# LT3762EUFD.net
KiCad netlist of a schematic drawn in Altium Designer
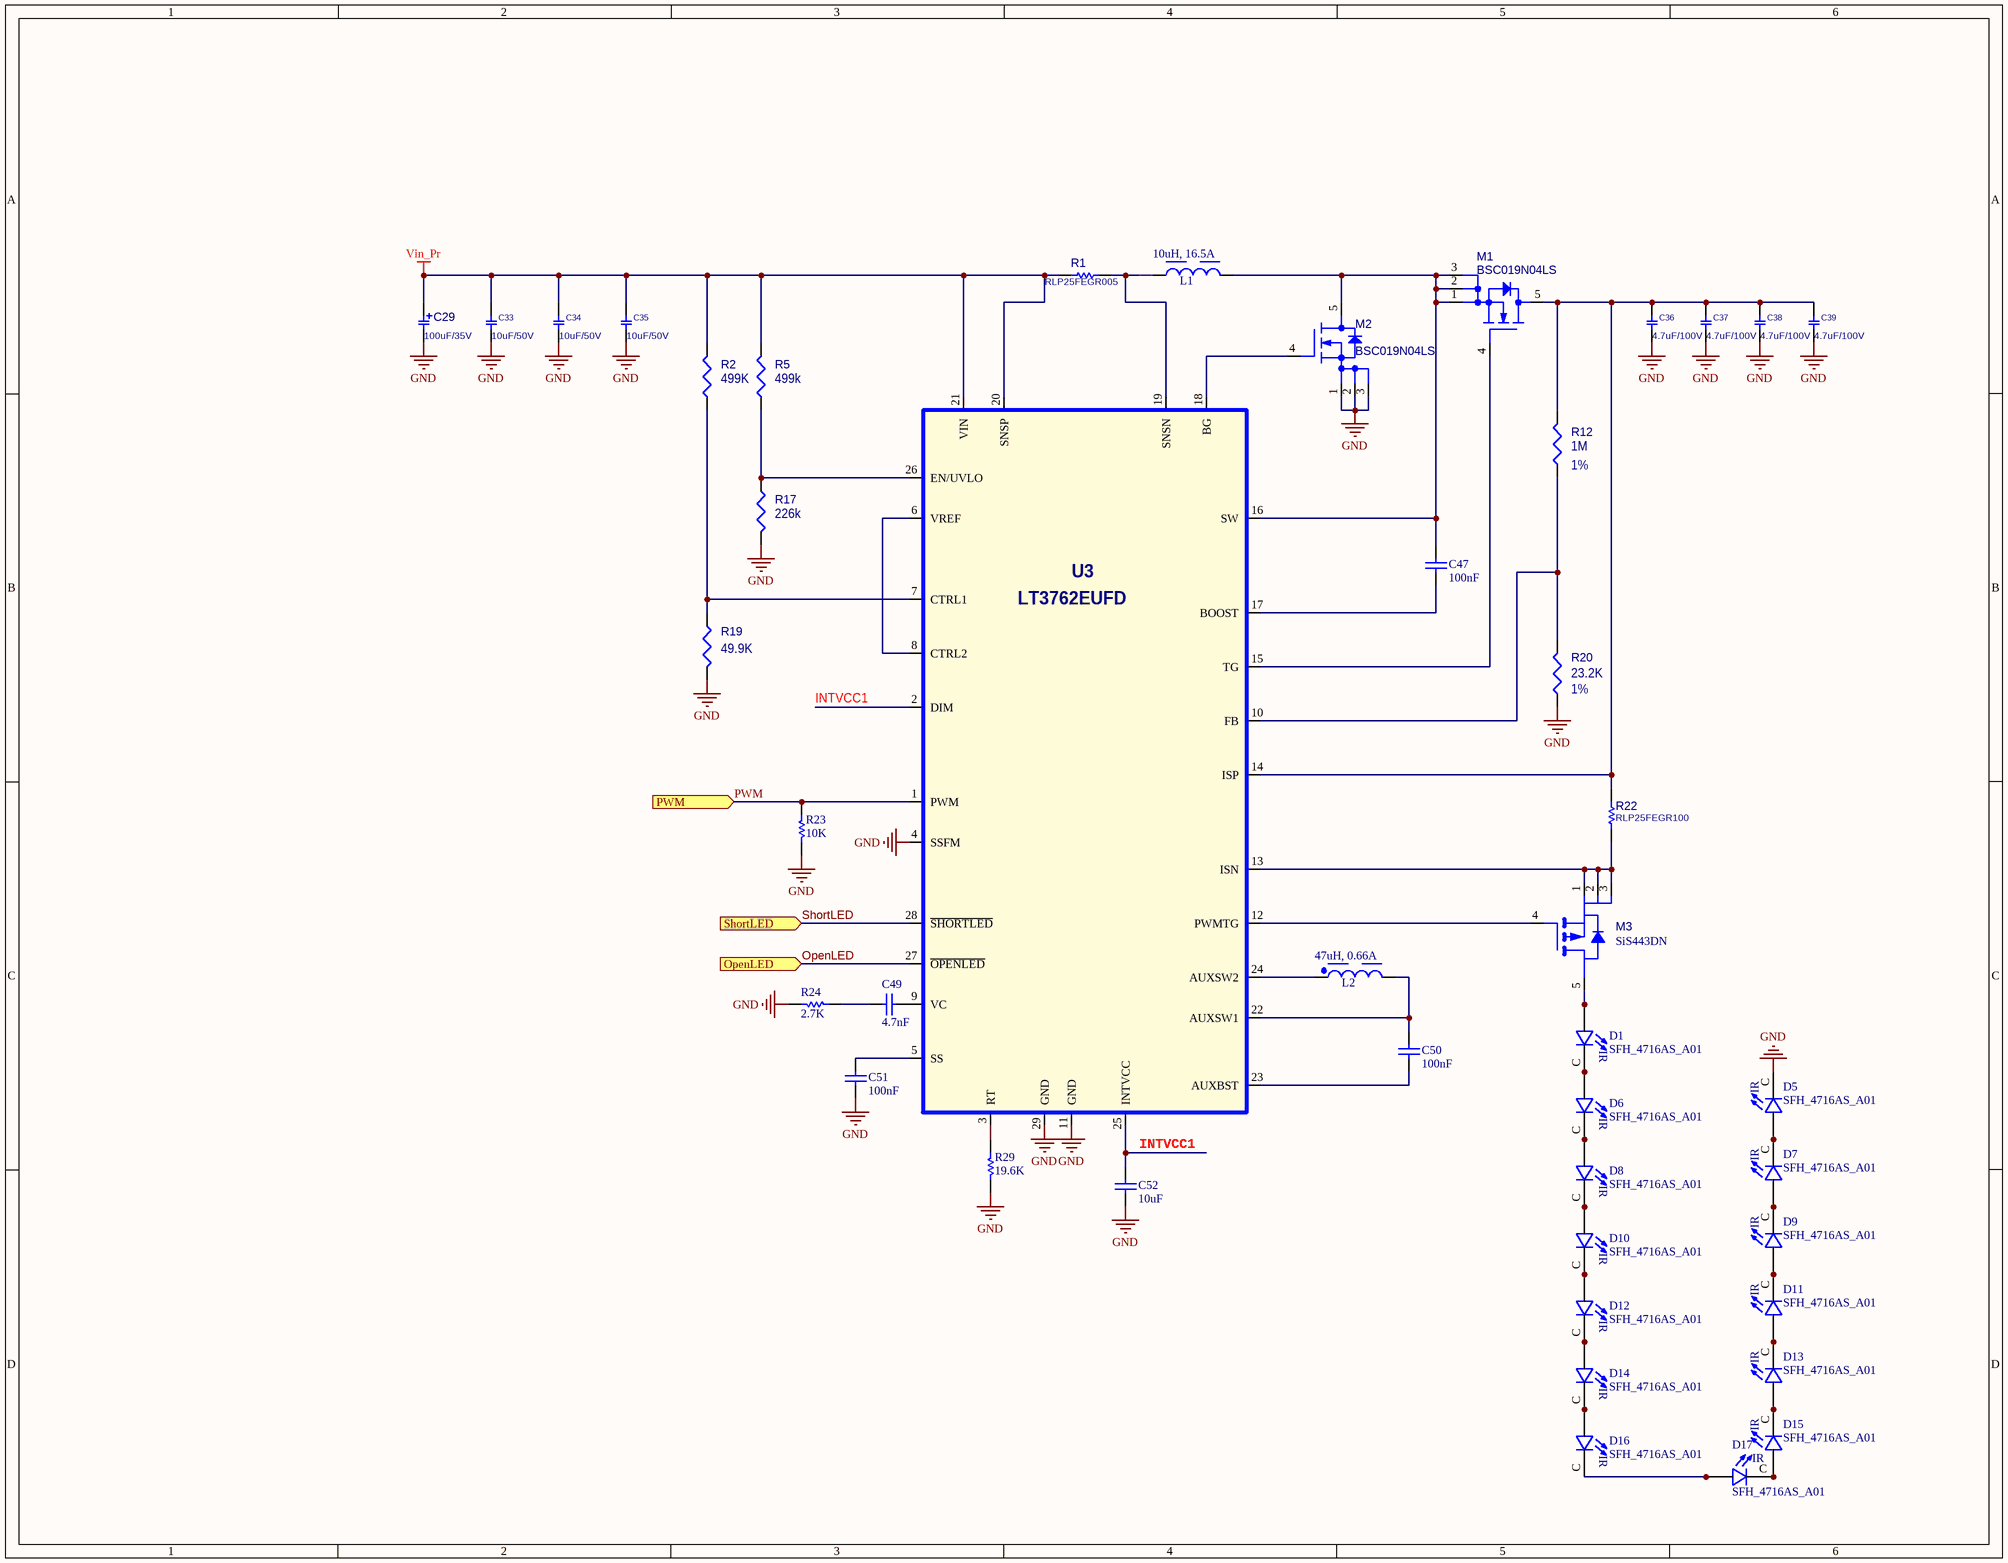
[diagram p0: LT3762EUFD.SchDoc]

(export (version "E")
  (design (tool "Eeschema 10.0.6"))
  (components
    (comp (ref "C29")
      (value "100uF/35V")
      (footprint "C_EL_D8L10")
      (description "CAP, SMD, ELEC,")
      (fields (field (name "MANF_P#") "MANF_PART#") (field (name "MANF") "MANF"))
      (libsource (lib "passive_smd") (part "CAP_SMD_EL_220uF_35v"))
    )
    (comp (ref "C33")
      (value "10uF/50V")
      (footprint "PASSIVE_SMD:C1210")
      (description "CAP, MLCC")
      (fields (field (name "MANF_P#") "MANF_PART#"))
      (libsource (lib "passive_smd") (part "CAP_SMD_MLCC_1210"))
    )
    (comp (ref "C34")
      (value "10uF/50V")
      (footprint "PASSIVE_SMD:C1210")
      (description "CAP, MLCC")
      (fields (field (name "MANF_P#") "MANF_PART#"))
      (libsource (lib "passive_smd") (part "CAP_SMD_MLCC_1210"))
    )
    (comp (ref "C35")
      (value "10uF/50V")
      (footprint "PASSIVE_SMD:C1210")
      (description "CAP, MLCC")
      (fields (field (name "MANF_P#") "MANF_PART#"))
      (libsource (lib "passive_smd") (part "CAP_SMD_MLCC_1210"))
    )
    (comp (ref "C36")
      (value "4.7uF/100V")
      (footprint "PASSIVE_SMD:C1210")
      (description "CAP, MLCC")
      (fields (field (name "MANF_P#") "MANF_PART#"))
      (libsource (lib "passive_smd") (part "CAP_SMD_MLCC_1210"))
    )
    (comp (ref "C37")
      (value "4.7uF/100V")
      (footprint "PASSIVE_SMD:C1210")
      (description "CAP, MLCC")
      (fields (field (name "MANF_P#") "MANF_PART#"))
      (libsource (lib "passive_smd") (part "CAP_SMD_MLCC_1210"))
    )
    (comp (ref "C38")
      (value "4.7uF/100V")
      (footprint "PASSIVE_SMD:C1210")
      (description "CAP, MLCC")
      (fields (field (name "MANF_P#") "MANF_PART#"))
      (libsource (lib "passive_smd") (part "CAP_SMD_MLCC_1210"))
    )
    (comp (ref "C39")
      (value "4.7uF/100V")
      (footprint "PASSIVE_SMD:C1210")
      (description "CAP, MLCC")
      (fields (field (name "MANF_P#") "MANF_PART#"))
      (libsource (lib "passive_smd") (part "CAP_SMD_MLCC_1210"))
    )
    (comp (ref "C47")
      (value "100nF")
      (footprint "C0603")
      (fields (field (name "PUBLISHER") "Altium Limited"))
      (libsource (lib "Miscellaneous Devices") (part "CAP"))
    )
    (comp (ref "C49")
      (value "4.7nF")
      (footprint "C0603")
      (fields (field (name "PUBLISHER") "Altium Limited"))
      (libsource (lib "Miscellaneous Devices") (part "CAP"))
    )
    (comp (ref "C50")
      (value "100nF")
      (footprint "C0603")
      (fields (field (name "PUBLISHER") "Altium Limited"))
      (libsource (lib "Miscellaneous Devices") (part "CAP"))
    )
    (comp (ref "C51")
      (value "100nF")
      (footprint "C0603")
      (fields (field (name "PUBLISHER") "Altium Limited"))
      (libsource (lib "Miscellaneous Devices") (part "CAP"))
    )
    (comp (ref "C52")
      (value "10uF")
      (footprint "C0603")
      (fields (field (name "PUBLISHER") "Altium Limited"))
      (libsource (lib "Miscellaneous Devices") (part "CAP"))
    )
    (comp (ref "D1")
      (value "SFH_4716AS_A01")
      (footprint "LED_SFH_4716AS_A01")
      (description "OSLON Black Series (850 nm) - 150Â°")
      (libsource (lib "SFH_4716AS_A01") (part "SFH_4716AS_A01"))
    )
    (comp (ref "D5")
      (value "SFH_4716AS_A01")
      (footprint "LED_SFH_4716AS_A01")
      (description "OSLON Black Series (850 nm) - 150Â°")
      (libsource (lib "SFH_4716AS_A01") (part "SFH_4716AS_A01"))
    )
    (comp (ref "D6")
      (value "SFH_4716AS_A01")
      (footprint "LED_SFH_4716AS_A01")
      (description "OSLON Black Series (850 nm) - 150Â°")
      (libsource (lib "SFH_4716AS_A01") (part "SFH_4716AS_A01"))
    )
    (comp (ref "D7")
      (value "SFH_4716AS_A01")
      (footprint "LED_SFH_4716AS_A01")
      (description "OSLON Black Series (850 nm) - 150Â°")
      (libsource (lib "SFH_4716AS_A01") (part "SFH_4716AS_A01"))
    )
    (comp (ref "D8")
      (value "SFH_4716AS_A01")
      (footprint "LED_SFH_4716AS_A01")
      (description "OSLON Black Series (850 nm) - 150Â°")
      (libsource (lib "SFH_4716AS_A01") (part "SFH_4716AS_A01"))
    )
    (comp (ref "D9")
      (value "SFH_4716AS_A01")
      (footprint "LED_SFH_4716AS_A01")
      (description "OSLON Black Series (850 nm) - 150Â°")
      (libsource (lib "SFH_4716AS_A01") (part "SFH_4716AS_A01"))
    )
    (comp (ref "D10")
      (value "SFH_4716AS_A01")
      (footprint "LED_SFH_4716AS_A01")
      (description "OSLON Black Series (850 nm) - 150Â°")
      (libsource (lib "SFH_4716AS_A01") (part "SFH_4716AS_A01"))
    )
    (comp (ref "D11")
      (value "SFH_4716AS_A01")
      (footprint "LED_SFH_4716AS_A01")
      (description "OSLON Black Series (850 nm) - 150Â°")
      (libsource (lib "SFH_4716AS_A01") (part "SFH_4716AS_A01"))
    )
    (comp (ref "D12")
      (value "SFH_4716AS_A01")
      (footprint "LED_SFH_4716AS_A01")
      (description "OSLON Black Series (850 nm) - 150Â°")
      (libsource (lib "SFH_4716AS_A01") (part "SFH_4716AS_A01"))
    )
    (comp (ref "D13")
      (value "SFH_4716AS_A01")
      (footprint "LED_SFH_4716AS_A01")
      (description "OSLON Black Series (850 nm) - 150Â°")
      (libsource (lib "SFH_4716AS_A01") (part "SFH_4716AS_A01"))
    )
    (comp (ref "D14")
      (value "SFH_4716AS_A01")
      (footprint "LED_SFH_4716AS_A01")
      (description "OSLON Black Series (850 nm) - 150Â°")
      (libsource (lib "SFH_4716AS_A01") (part "SFH_4716AS_A01"))
    )
    (comp (ref "D15")
      (value "SFH_4716AS_A01")
      (footprint "LED_SFH_4716AS_A01")
      (description "OSLON Black Series (850 nm) - 150Â°")
      (libsource (lib "SFH_4716AS_A01") (part "SFH_4716AS_A01"))
    )
    (comp (ref "D16")
      (value "SFH_4716AS_A01")
      (footprint "LED_SFH_4716AS_A01")
      (description "OSLON Black Series (850 nm) - 150Â°")
      (libsource (lib "SFH_4716AS_A01") (part "SFH_4716AS_A01"))
    )
    (comp (ref "D17")
      (value "SFH_4716AS_A01")
      (footprint "LED_SFH_4716AS_A01")
      (description "OSLON Black Series (850 nm) - 150Â°")
      (libsource (lib "SFH_4716AS_A01") (part "SFH_4716AS_A01"))
    )
    (comp (ref "L1")
      (value "10uH, 16.5A")
      (footprint "WE-HCI_1890")
      (description "WE-HCI SMT Flat Wire High Current Inductor, size 1890, 10uH, 16.5A, 6.9mOhm")
      (fields
        (field (name "MANUFACTURER PART NUMBER") "74435561100")
        (field (name "MANUFACTURER") "Wurth Elektronik")
      )
      (libsource (lib "WE - Passive Components") (part "Inductor - 3"))
    )
    (comp (ref "L2")
      (value "47uH, 0.66A")
      (footprint "WE-SPC_4828")
      (description "WE-SPC SMT Power Inductor, size 4828, 47uH, 0.66A, 0.608Ohm")
      (fields
        (field (name "MANUFACTURER PART NUMBER") "74408942470")
        (field (name "MANUFACTURER") "Wurth Elektronik")
      )
      (libsource (lib "WE - Passive Components") (part "Inductor - 2"))
    )
    (comp (ref "M1") (value "BSC019N04LS") (footprint "PG-TDSON-8") (libsource (lib "*") (part "2N7000_6")))
    (comp (ref "M2") (value "BSC019N04LS") (footprint "PG-TDSON-8") (libsource (lib "*") (part "2N7000_6")))
    (comp (ref "M3")
      (value "SiS443DN")
      (footprint "POWERPAK-1212-8-S-5P")
      (libsource (lib "*") (part "SI4463BDY_1"))
    )
    (comp (ref "R1")
      (value "RLP25FEGR005")
      (footprint "R2512")
      (description "3W 5mΩ ±50ppm/℃ ±1% 2512 Current Sense Shunt Resistors")
      (libsource (lib "passive_smd") (part "RES_SMD_2512"))
    )
    (comp (ref "R2") (value "499K") (footprint "R0603") (libsource (lib "*") (part "RES0402")))
    (comp (ref "R5") (value "499k") (footprint "R0603") (libsource (lib "*") (part "RES0402")))
    (comp (ref "R12")
      (value "1M")
      (footprint "R0603")
      (fields (field (name "6TH PART FIELD") "1%"))
      (libsource (lib "*") (part "RES0402"))
    )
    (comp (ref "R17") (value "226k") (footprint "R0603") (libsource (lib "*") (part "RES0402")))
    (comp (ref "R19") (value "49.9K") (footprint "R0603") (libsource (lib "*") (part "RES0402")))
    (comp (ref "R20")
      (value "23.2K")
      (footprint "R0603")
      (fields (field (name "6TH PART FIELD") "1%"))
      (libsource (lib "*") (part "RES0402"))
    )
    (comp (ref "R22")
      (value "RLP25FEGR100")
      (footprint "R2512")
      (description "3W 100mΩ ±50ppm/℃ ±1% 2512 Current Sense Shunt Resistors")
      (libsource (lib "passive_smd") (part "RES_SMD_2512"))
    )
    (comp (ref "R23")
      (value "10K")
      (footprint "R0603")
      (fields (field (name "PUBLISHER") "Altium Limited"))
      (libsource (lib "Miscellaneous Devices") (part "Res1"))
    )
    (comp (ref "R24")
      (value "2.7K")
      (footprint "R0603")
      (fields (field (name "PUBLISHER") "Altium Limited"))
      (libsource (lib "Miscellaneous Devices") (part "Res1"))
    )
    (comp (ref "R29")
      (value "19.6K")
      (footprint "R0603")
      (fields (field (name "PUBLISHER") "Altium Limited"))
      (libsource (lib "Miscellaneous Devices") (part "Res1"))
    )
    (comp (ref "U3")
      (value "LT3762EUFD")
      (footprint "QFN-28-4X5")
      (libsource (lib "*") (part "LT3932EFE_37"))
    )
  )
  (nets
    (net (code "1") (name "/INTVCC1") (class "Default")
      (node (ref "C52") (pin "1") (pinfunction "1_1") (pintype "passive"))
      (node (ref "U3") (pin "2") (pinfunction "DIM_2") (pintype "passive"))
      (node (ref "U3") (pin "25") (pinfunction "INTVCC_25") (pintype "passive"))
    )
    (net (code "2") (name "/OpenLED") (class "Default")
      (node (ref "U3") (pin "27") (pinfunction "~{OPENLED}_27") (pintype "passive"))
    )
    (net (code "3") (name "/PWM") (class "Default")
      (node (ref "R23") (pin "1") (pinfunction "1_1") (pintype "passive"))
      (node (ref "U3") (pin "1") (pinfunction "PWM_1") (pintype "passive"))
    )
    (net (code "4") (name "/ShortLED") (class "Default")
      (node (ref "U3") (pin "28") (pinfunction "~{SHORTLED}_28") (pintype "passive"))
    )
    (net (code "5") (name "GND") (class "Default")
      (node (ref "C29") (pin "2") (pinfunction "2_2") (pintype "passive"))
      (node (ref "C33") (pin "1") (pinfunction "1_1") (pintype "passive"))
      (node (ref "C34") (pin "1") (pinfunction "1_1") (pintype "passive"))
      (node (ref "C35") (pin "1") (pinfunction "1_1") (pintype "passive"))
      (node (ref "C36") (pin "1") (pinfunction "1_1") (pintype "passive"))
      (node (ref "C37") (pin "1") (pinfunction "1_1") (pintype "passive"))
      (node (ref "C38") (pin "1") (pinfunction "1_1") (pintype "passive"))
      (node (ref "C39") (pin "1") (pinfunction "1_1") (pintype "passive"))
      (node (ref "C51") (pin "2") (pinfunction "2_2") (pintype "passive"))
      (node (ref "C52") (pin "2") (pinfunction "2_2") (pintype "passive"))
      (node (ref "D5") (pin "C") (pinfunction "C_C") (pintype "passive"))
      (node (ref "M2") (pin "1") (pinfunction "SOURCE_1") (pintype "passive"))
      (node (ref "M2") (pin "2") (pinfunction "SOURCE_2") (pintype "passive"))
      (node (ref "M2") (pin "3") (pinfunction "SOURCE_3") (pintype "passive"))
      (node (ref "R17") (pin "1") (pinfunction "1_1") (pintype "passive"))
      (node (ref "R19") (pin "2") (pinfunction "2_2") (pintype "passive"))
      (node (ref "R20") (pin "1") (pinfunction "1_1") (pintype "passive"))
      (node (ref "R23") (pin "2") (pinfunction "2_2") (pintype "passive"))
      (node (ref "R24") (pin "2") (pinfunction "2_2") (pintype "passive"))
      (node (ref "R29") (pin "2") (pinfunction "2_2") (pintype "passive"))
      (node (ref "U3") (pin "11") (pinfunction "GND_11") (pintype "passive"))
      (node (ref "U3") (pin "29") (pinfunction "GND_29") (pintype "passive"))
      (node (ref "U3") (pin "4") (pinfunction "SSFM_4") (pintype "passive"))
    )
    (net (code "6") (name "Net-(C49-Pad2)") (class "Default")
      (node (ref "C49") (pin "2") (pinfunction "2_2") (pintype "passive"))
      (node (ref "R24") (pin "1") (pinfunction "1_1") (pintype "passive"))
    )
    (net (code "7") (name "Net-(D1-A-PadA1)") (class "Default")
      (node (ref "D1") (pin "A1") (pinfunction "A_A1") (pintype "passive"))
      (node (ref "D1") (pin "A2") (pinfunction "A_A2") (pintype "passive"))
      (node (ref "M3") (pin "5") (pinfunction "5_5") (pintype "passive"))
    )
    (net (code "8") (name "Net-(D1-PadC)") (class "Default")
      (node (ref "D1") (pin "C") (pinfunction "C_C") (pintype "passive"))
      (node (ref "D6") (pin "A1") (pinfunction "A_A1") (pintype "passive"))
      (node (ref "D6") (pin "A2") (pinfunction "A_A2") (pintype "passive"))
    )
    (net (code "9") (name "Net-(D5-A-PadA1)") (class "Default")
      (node (ref "D5") (pin "A1") (pinfunction "A_A1") (pintype "passive"))
      (node (ref "D5") (pin "A2") (pinfunction "A_A2") (pintype "passive"))
      (node (ref "D7") (pin "C") (pinfunction "C_C") (pintype "passive"))
    )
    (net (code "10") (name "Net-(D6-PadC)") (class "Default")
      (node (ref "D6") (pin "C") (pinfunction "C_C") (pintype "passive"))
      (node (ref "D8") (pin "A1") (pinfunction "A_A1") (pintype "passive"))
      (node (ref "D8") (pin "A2") (pinfunction "A_A2") (pintype "passive"))
    )
    (net (code "11") (name "Net-(D7-A-PadA1)") (class "Default")
      (node (ref "D7") (pin "A1") (pinfunction "A_A1") (pintype "passive"))
      (node (ref "D7") (pin "A2") (pinfunction "A_A2") (pintype "passive"))
      (node (ref "D9") (pin "C") (pinfunction "C_C") (pintype "passive"))
    )
    (net (code "12") (name "Net-(D10-A-PadA1)") (class "Default")
      (node (ref "D10") (pin "A1") (pinfunction "A_A1") (pintype "passive"))
      (node (ref "D10") (pin "A2") (pinfunction "A_A2") (pintype "passive"))
      (node (ref "D8") (pin "C") (pinfunction "C_C") (pintype "passive"))
    )
    (net (code "13") (name "Net-(D10-PadC)") (class "Default")
      (node (ref "D10") (pin "C") (pinfunction "C_C") (pintype "passive"))
      (node (ref "D12") (pin "A1") (pinfunction "A_A1") (pintype "passive"))
      (node (ref "D12") (pin "A2") (pinfunction "A_A2") (pintype "passive"))
    )
    (net (code "14") (name "Net-(D11-A-PadA1)") (class "Default")
      (node (ref "D11") (pin "A1") (pinfunction "A_A1") (pintype "passive"))
      (node (ref "D11") (pin "A2") (pinfunction "A_A2") (pintype "passive"))
      (node (ref "D13") (pin "C") (pinfunction "C_C") (pintype "passive"))
    )
    (net (code "15") (name "Net-(D11-PadC)") (class "Default")
      (node (ref "D11") (pin "C") (pinfunction "C_C") (pintype "passive"))
      (node (ref "D9") (pin "A1") (pinfunction "A_A1") (pintype "passive"))
      (node (ref "D9") (pin "A2") (pinfunction "A_A2") (pintype "passive"))
    )
    (net (code "16") (name "Net-(D12-PadC)") (class "Default")
      (node (ref "D12") (pin "C") (pinfunction "C_C") (pintype "passive"))
      (node (ref "D14") (pin "A1") (pinfunction "A_A1") (pintype "passive"))
      (node (ref "D14") (pin "A2") (pinfunction "A_A2") (pintype "passive"))
    )
    (net (code "17") (name "Net-(D13-A-PadA1)") (class "Default")
      (node (ref "D13") (pin "A1") (pinfunction "A_A1") (pintype "passive"))
      (node (ref "D13") (pin "A2") (pinfunction "A_A2") (pintype "passive"))
      (node (ref "D15") (pin "C") (pinfunction "C_C") (pintype "passive"))
    )
    (net (code "18") (name "Net-(D14-PadC)") (class "Default")
      (node (ref "D14") (pin "C") (pinfunction "C_C") (pintype "passive"))
      (node (ref "D16") (pin "A1") (pinfunction "A_A1") (pintype "passive"))
      (node (ref "D16") (pin "A2") (pinfunction "A_A2") (pintype "passive"))
    )
    (net (code "19") (name "Net-(D15-A-PadA1)") (class "Default")
      (node (ref "D15") (pin "A1") (pinfunction "A_A1") (pintype "passive"))
      (node (ref "D15") (pin "A2") (pinfunction "A_A2") (pintype "passive"))
      (node (ref "D17") (pin "C") (pinfunction "C_C") (pintype "passive"))
    )
    (net (code "20") (name "Net-(D16-PadC)") (class "Default")
      (node (ref "D16") (pin "C") (pinfunction "C_C") (pintype "passive"))
      (node (ref "D17") (pin "A1") (pinfunction "A_A1") (pintype "passive"))
      (node (ref "D17") (pin "A2") (pinfunction "A_A2") (pintype "passive"))
    )
    (net (code "21") (name "Net-(M1-DRAIN)") (class "Default")
      (node (ref "C36") (pin "2") (pinfunction "2_2") (pintype "passive"))
      (node (ref "C37") (pin "2") (pinfunction "2_2") (pintype "passive"))
      (node (ref "C38") (pin "2") (pinfunction "2_2") (pintype "passive"))
      (node (ref "C39") (pin "2") (pinfunction "2_2") (pintype "passive"))
      (node (ref "M1") (pin "5") (pinfunction "DRAIN_5") (pintype "passive"))
      (node (ref "R12") (pin "2") (pinfunction "2_2") (pintype "passive"))
      (node (ref "R22") (pin "2") (pinfunction "2_2") (pintype "passive"))
      (node (ref "U3") (pin "14") (pinfunction "ISP_14") (pintype "passive"))
    )
    (net (code "22") (name "Net-(M1-GATE)") (class "Default")
      (node (ref "M1") (pin "4") (pinfunction "GATE_4") (pintype "passive"))
      (node (ref "U3") (pin "15") (pinfunction "TG_15") (pintype "passive"))
    )
    (net (code "23") (name "Net-(M2-DRAIN)") (class "Default")
      (node (ref "C47") (pin "1") (pinfunction "1_1") (pintype "passive"))
      (node (ref "L1") (pin "2") (pinfunction "2_2") (pintype "passive"))
      (node (ref "M1") (pin "1") (pinfunction "SOURCE_1") (pintype "passive"))
      (node (ref "M1") (pin "2") (pinfunction "SOURCE_2") (pintype "passive"))
      (node (ref "M1") (pin "3") (pinfunction "SOURCE_3") (pintype "passive"))
      (node (ref "M2") (pin "5") (pinfunction "DRAIN_5") (pintype "passive"))
      (node (ref "U3") (pin "16") (pinfunction "SW_16") (pintype "passive"))
    )
    (net (code "24") (name "Net-(M2-GATE)") (class "Default")
      (node (ref "M2") (pin "4") (pinfunction "GATE_4") (pintype "passive"))
      (node (ref "U3") (pin "18") (pinfunction "BG_18") (pintype "passive"))
    )
    (net (code "25") (name "Net-(U3-AUXBST)") (class "Default")
      (node (ref "C50") (pin "2") (pinfunction "2_2") (pintype "passive"))
      (node (ref "U3") (pin "23") (pinfunction "AUXBST_23") (pintype "passive"))
    )
    (net (code "26") (name "Net-(U3-AUXSW1)") (class "Default")
      (node (ref "C50") (pin "1") (pinfunction "1_1") (pintype "passive"))
      (node (ref "L2") (pin "2") (pinfunction "2_2") (pintype "passive"))
      (node (ref "U3") (pin "22") (pinfunction "AUXSW1_22") (pintype "passive"))
    )
    (net (code "27") (name "Net-(U3-AUXSW2)") (class "Default")
      (node (ref "L2") (pin "1") (pinfunction "1_1") (pintype "passive"))
      (node (ref "U3") (pin "24") (pinfunction "AUXSW2_24") (pintype "passive"))
    )
    (net (code "28") (name "Net-(U3-BOOST)") (class "Default")
      (node (ref "C47") (pin "2") (pinfunction "2_2") (pintype "passive"))
      (node (ref "U3") (pin "17") (pinfunction "BOOST_17") (pintype "passive"))
    )
    (net (code "29") (name "Net-(U3-CTRL1)") (class "Default")
      (node (ref "R19") (pin "1") (pinfunction "1_1") (pintype "passive"))
      (node (ref "R2") (pin "1") (pinfunction "1_1") (pintype "passive"))
      (node (ref "U3") (pin "7") (pinfunction "CTRL1_7") (pintype "passive"))
    )
    (net (code "30") (name "Net-(U3-CTRL2)") (class "Default")
      (node (ref "U3") (pin "6") (pinfunction "VREF_6") (pintype "passive"))
      (node (ref "U3") (pin "8") (pinfunction "CTRL2_8") (pintype "passive"))
    )
    (net (code "31") (name "Net-(U3-EN{slash}UVLO)") (class "Default")
      (node (ref "R17") (pin "2") (pinfunction "2_2") (pintype "passive"))
      (node (ref "R5") (pin "1") (pinfunction "1_1") (pintype "passive"))
      (node (ref "U3") (pin "26") (pinfunction "EN/UVLO_26") (pintype "passive"))
    )
    (net (code "32") (name "Net-(U3-FB)") (class "Default")
      (node (ref "R12") (pin "1") (pinfunction "1_1") (pintype "passive"))
      (node (ref "R20") (pin "2") (pinfunction "2_2") (pintype "passive"))
      (node (ref "U3") (pin "10") (pinfunction "FB_10") (pintype "passive"))
    )
    (net (code "33") (name "Net-(U3-ISN)") (class "Default")
      (node (ref "M3") (pin "1") (pinfunction "1_1") (pintype "passive"))
      (node (ref "M3") (pin "2") (pinfunction "2_2") (pintype "passive"))
      (node (ref "M3") (pin "3") (pinfunction "3_3") (pintype "passive"))
      (node (ref "R22") (pin "1") (pinfunction "1_1") (pintype "passive"))
      (node (ref "U3") (pin "13") (pinfunction "ISN_13") (pintype "passive"))
    )
    (net (code "34") (name "Net-(U3-PWMTG)") (class "Default")
      (node (ref "M3") (pin "4") (pinfunction "4_4") (pintype "passive"))
      (node (ref "U3") (pin "12") (pinfunction "PWMTG_12") (pintype "passive"))
    )
    (net (code "35") (name "Net-(U3-RT)") (class "Default")
      (node (ref "R29") (pin "1") (pinfunction "1_1") (pintype "passive"))
      (node (ref "U3") (pin "3") (pinfunction "RT_3") (pintype "passive"))
    )
    (net (code "36") (name "Net-(U3-SNSN)") (class "Default")
      (node (ref "L1") (pin "1") (pinfunction "1_1") (pintype "passive"))
      (node (ref "R1") (pin "2") (pinfunction "2_2") (pintype "passive"))
      (node (ref "U3") (pin "19") (pinfunction "SNSN_19") (pintype "passive"))
    )
    (net (code "37") (name "Net-(U3-SS)") (class "Default")
      (node (ref "C51") (pin "1") (pinfunction "1_1") (pintype "passive"))
      (node (ref "U3") (pin "5") (pinfunction "SS_5") (pintype "passive"))
    )
    (net (code "38") (name "Net-(U3-VC)") (class "Default")
      (node (ref "C49") (pin "1") (pinfunction "1_1") (pintype "passive"))
      (node (ref "U3") (pin "9") (pinfunction "VC_9") (pintype "passive"))
    )
    (net (code "39") (name "Vin_Pr") (class "Default")
      (node (ref "C29") (pin "1") (pinfunction "1_1") (pintype "passive"))
      (node (ref "C33") (pin "2") (pinfunction "2_2") (pintype "passive"))
      (node (ref "C34") (pin "2") (pinfunction "2_2") (pintype "passive"))
      (node (ref "C35") (pin "2") (pinfunction "2_2") (pintype "passive"))
      (node (ref "R1") (pin "1") (pinfunction "1_1") (pintype "passive"))
      (node (ref "R2") (pin "2") (pinfunction "2_2") (pintype "passive"))
      (node (ref "R5") (pin "2") (pinfunction "2_2") (pintype "passive"))
      (node (ref "U3") (pin "20") (pinfunction "SNSP_20") (pintype "passive"))
      (node (ref "U3") (pin "21") (pinfunction "VIN_21") (pintype "passive"))
    )
  )
)
